# Carte_USB.net
KiCad netlist of a schematic drawn in EAGLE
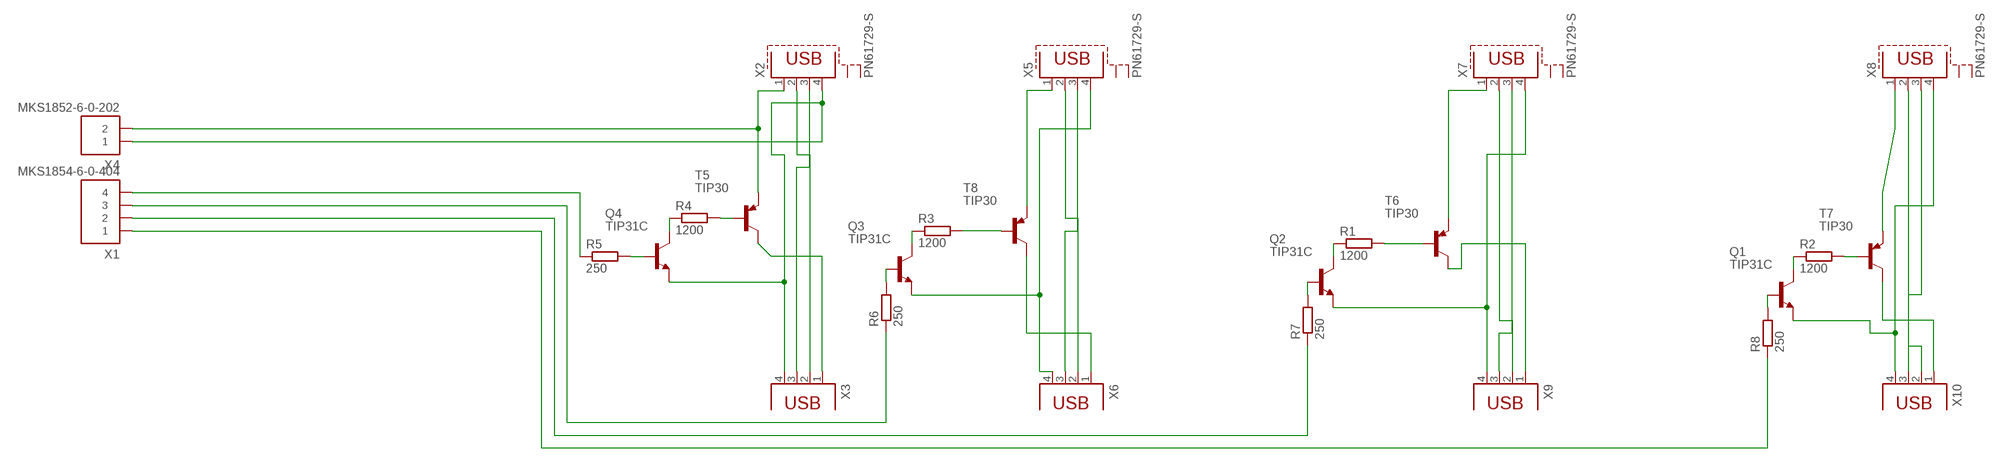
[diagram p0: schematic, sheet 1]

(export (version "E")
  (design (tool "Eeschema 10.0.6"))
  (components
    (comp (ref "Q1")
      (value "TIP31C")
      (footprint "eagle-import:TO220")
      (libsource (lib "eagle-import") (part "TIP31C"))
    )
    (comp (ref "Q2")
      (value "TIP31C")
      (footprint "eagle-import:TO220")
      (libsource (lib "eagle-import") (part "TIP31C"))
    )
    (comp (ref "Q3")
      (value "TIP31C")
      (footprint "eagle-import:TO220")
      (libsource (lib "eagle-import") (part "TIP31C"))
    )
    (comp (ref "Q4")
      (value "TIP31C")
      (footprint "eagle-import:TO220")
      (libsource (lib "eagle-import") (part "TIP31C"))
    )
    (comp (ref "R1")
      (value "1200")
      (footprint "eagle-import:0207_10")
      (libsource (lib "eagle-import") (part "R-EU_0207/10"))
    )
    (comp (ref "R2")
      (value "1200")
      (footprint "eagle-import:0207_10")
      (libsource (lib "eagle-import") (part "R-EU_0207/10"))
    )
    (comp (ref "R3")
      (value "1200")
      (footprint "eagle-import:0207_10")
      (libsource (lib "eagle-import") (part "R-EU_0207/10"))
    )
    (comp (ref "R4")
      (value "1200")
      (footprint "eagle-import:0207_10")
      (libsource (lib "eagle-import") (part "R-EU_0207/10"))
    )
    (comp (ref "R5")
      (value "250")
      (footprint "eagle-import:0207_10")
      (libsource (lib "eagle-import") (part "R-EU_0207/10"))
    )
    (comp (ref "R6")
      (value "250")
      (footprint "eagle-import:0207_12")
      (libsource (lib "eagle-import") (part "R-EU_0207/12"))
    )
    (comp (ref "R7")
      (value "250")
      (footprint "eagle-import:0207_10")
      (libsource (lib "eagle-import") (part "R-EU_0207/10"))
    )
    (comp (ref "R8")
      (value "250")
      (footprint "eagle-import:0207_10")
      (libsource (lib "eagle-import") (part "R-EU_0207/10"))
    )
    (comp (ref "T5")
      (value "TIP30")
      (footprint "eagle-import:TO220")
      (libsource (lib "eagle-import") (part "TIP30"))
    )
    (comp (ref "T6")
      (value "TIP30")
      (footprint "eagle-import:TO220")
      (libsource (lib "eagle-import") (part "TIP30"))
    )
    (comp (ref "T7")
      (value "TIP30")
      (footprint "eagle-import:TO220")
      (libsource (lib "eagle-import") (part "TIP30"))
    )
    (comp (ref "T8")
      (value "TIP30")
      (footprint "eagle-import:TO220")
      (libsource (lib "eagle-import") (part "TIP30"))
    )
    (comp (ref "X1")
      (value "MKS1854-6-0-404")
      (footprint "eagle-import:MKS1854-6-0-404")
      (libsource (lib "eagle-import") (part "MKS1854-6-0-404"))
    )
    (comp (ref "X2")
      (value "PN61729-S")
      (footprint "eagle-import:PN61729-S")
      (libsource (lib "eagle-import") (part "PN61729-S"))
    )
    (comp (ref "X3")
      (value "PN87520")
      (footprint "eagle-import:PN87520")
      (libsource (lib "eagle-import") (part "PN87520"))
    )
    (comp (ref "X4")
      (value "MKS1852-6-0-202")
      (footprint "eagle-import:MKS1852-6-0-202")
      (libsource (lib "eagle-import") (part "MKS1852-6-0-202"))
    )
    (comp (ref "X5")
      (value "PN61729-S")
      (footprint "eagle-import:PN61729-S")
      (libsource (lib "eagle-import") (part "PN61729-S"))
    )
    (comp (ref "X6")
      (value "PN87520")
      (footprint "eagle-import:PN87520")
      (libsource (lib "eagle-import") (part "PN87520"))
    )
    (comp (ref "X7")
      (value "PN61729-S")
      (footprint "eagle-import:PN61729-S")
      (libsource (lib "eagle-import") (part "PN61729-S"))
    )
    (comp (ref "X8")
      (value "PN61729-S")
      (footprint "eagle-import:PN61729-S")
      (libsource (lib "eagle-import") (part "PN61729-S"))
    )
    (comp (ref "X9")
      (value "PN87520")
      (footprint "eagle-import:PN87520")
      (libsource (lib "eagle-import") (part "PN87520"))
    )
    (comp (ref "X10")
      (value "PN87520")
      (footprint "eagle-import:PN87520")
      (libsource (lib "eagle-import") (part "PN87520"))
    )
  )
  (nets
    (net (code "1") (name "Net-(Q1-B)") (class "Default")
      (node (ref "Q1") (pin "1") (pinfunction "B_1") (pintype "passive"))
      (node (ref "R8") (pin "2") (pinfunction "2_2") (pintype "passive"))
    )
    (net (code "2") (name "Net-(Q1-C)") (class "Default")
      (node (ref "Q1") (pin "2") (pinfunction "C_2") (pintype "passive"))
      (node (ref "R2") (pin "1") (pinfunction "1_1") (pintype "passive"))
    )
    (net (code "3") (name "Net-(Q1-E)") (class "Default")
      (node (ref "Q1") (pin "3") (pinfunction "E_3") (pintype "passive"))
      (node (ref "X10") (pin "4") (pinfunction "4_4") (pintype "passive"))
      (node (ref "X8") (pin "4") (pinfunction "4_4") (pintype "passive"))
    )
    (net (code "4") (name "Net-(Q2-B)") (class "Default")
      (node (ref "Q2") (pin "1") (pinfunction "B_1") (pintype "passive"))
      (node (ref "R7") (pin "2") (pinfunction "2_2") (pintype "passive"))
    )
    (net (code "5") (name "Net-(Q2-C)") (class "Default")
      (node (ref "Q2") (pin "2") (pinfunction "C_2") (pintype "passive"))
      (node (ref "R1") (pin "1") (pinfunction "1_1") (pintype "passive"))
    )
    (net (code "6") (name "Net-(Q2-E)") (class "Default")
      (node (ref "Q2") (pin "3") (pinfunction "E_3") (pintype "passive"))
      (node (ref "X7") (pin "4") (pinfunction "4_4") (pintype "passive"))
      (node (ref "X9") (pin "4") (pinfunction "4_4") (pintype "passive"))
    )
    (net (code "7") (name "Net-(Q3-B)") (class "Default")
      (node (ref "Q3") (pin "1") (pinfunction "B_1") (pintype "passive"))
      (node (ref "R6") (pin "2") (pinfunction "2_2") (pintype "passive"))
    )
    (net (code "8") (name "Net-(Q3-C)") (class "Default")
      (node (ref "Q3") (pin "2") (pinfunction "C_2") (pintype "passive"))
      (node (ref "R3") (pin "1") (pinfunction "1_1") (pintype "passive"))
    )
    (net (code "9") (name "Net-(Q3-E)") (class "Default")
      (node (ref "Q3") (pin "3") (pinfunction "E_3") (pintype "passive"))
      (node (ref "X5") (pin "4") (pinfunction "4_4") (pintype "passive"))
      (node (ref "X6") (pin "4") (pinfunction "4_4") (pintype "passive"))
    )
    (net (code "10") (name "Net-(Q4-B)") (class "Default")
      (node (ref "Q4") (pin "1") (pinfunction "B_1") (pintype "passive"))
      (node (ref "R5") (pin "2") (pinfunction "2_2") (pintype "passive"))
    )
    (net (code "11") (name "Net-(Q4-C)") (class "Default")
      (node (ref "Q4") (pin "2") (pinfunction "C_2") (pintype "passive"))
      (node (ref "R4") (pin "1") (pinfunction "1_1") (pintype "passive"))
    )
    (net (code "12") (name "Net-(Q4-E)") (class "Default")
      (node (ref "Q4") (pin "3") (pinfunction "E_3") (pintype "passive"))
      (node (ref "X2") (pin "4") (pinfunction "4_4") (pintype "passive"))
      (node (ref "X3") (pin "4") (pinfunction "4_4") (pintype "passive"))
      (node (ref "X4") (pin "1") (pinfunction "1_1") (pintype "input"))
    )
    (net (code "13") (name "Net-(R5-Pad1)") (class "Default")
      (node (ref "R5") (pin "1") (pinfunction "1_1") (pintype "passive"))
      (node (ref "X1") (pin "4") (pinfunction "4_4") (pintype "input"))
    )
    (net (code "14") (name "Net-(R6-Pad1)") (class "Default")
      (node (ref "R6") (pin "1") (pinfunction "1_1") (pintype "passive"))
      (node (ref "X1") (pin "3") (pinfunction "3_3") (pintype "input"))
    )
    (net (code "15") (name "Net-(R7-Pad1)") (class "Default")
      (node (ref "R7") (pin "1") (pinfunction "1_1") (pintype "passive"))
      (node (ref "X1") (pin "2") (pinfunction "2_2") (pintype "input"))
    )
    (net (code "16") (name "Net-(R8-Pad1)") (class "Default")
      (node (ref "R8") (pin "1") (pinfunction "1_1") (pintype "passive"))
      (node (ref "X1") (pin "1") (pinfunction "1_1") (pintype "input"))
    )
    (net (code "17") (name "Net-(T5-B)") (class "Default")
      (node (ref "R4") (pin "2") (pinfunction "2_2") (pintype "passive"))
      (node (ref "T5") (pin "1") (pinfunction "B_1") (pintype "passive"))
    )
    (net (code "18") (name "Net-(T5-C)") (class "Default")
      (node (ref "T5") (pin "2") (pinfunction "C_2") (pintype "passive"))
      (node (ref "X3") (pin "1") (pinfunction "1_1") (pintype "passive"))
    )
    (net (code "19") (name "Net-(T5-E)") (class "Default")
      (node (ref "T5") (pin "3") (pinfunction "E_3") (pintype "passive"))
      (node (ref "X2") (pin "1") (pinfunction "1_1") (pintype "passive"))
      (node (ref "X4") (pin "2") (pinfunction "2_2") (pintype "input"))
    )
    (net (code "20") (name "Net-(T6-B)") (class "Default")
      (node (ref "R1") (pin "2") (pinfunction "2_2") (pintype "passive"))
      (node (ref "T6") (pin "1") (pinfunction "B_1") (pintype "passive"))
    )
    (net (code "21") (name "Net-(T6-C)") (class "Default")
      (node (ref "T6") (pin "2") (pinfunction "C_2") (pintype "passive"))
      (node (ref "X9") (pin "1") (pinfunction "1_1") (pintype "passive"))
    )
    (net (code "22") (name "Net-(T6-E)") (class "Default")
      (node (ref "T6") (pin "3") (pinfunction "E_3") (pintype "passive"))
      (node (ref "X7") (pin "1") (pinfunction "1_1") (pintype "passive"))
    )
    (net (code "23") (name "Net-(T7-B)") (class "Default")
      (node (ref "R2") (pin "2") (pinfunction "2_2") (pintype "passive"))
      (node (ref "T7") (pin "1") (pinfunction "B_1") (pintype "passive"))
    )
    (net (code "24") (name "Net-(T7-C)") (class "Default")
      (node (ref "T7") (pin "2") (pinfunction "C_2") (pintype "passive"))
      (node (ref "X10") (pin "1") (pinfunction "1_1") (pintype "passive"))
    )
    (net (code "25") (name "Net-(T7-E)") (class "Default")
      (node (ref "T7") (pin "3") (pinfunction "E_3") (pintype "passive"))
      (node (ref "X8") (pin "1") (pinfunction "1_1") (pintype "passive"))
    )
    (net (code "26") (name "Net-(T8-B)") (class "Default")
      (node (ref "R3") (pin "2") (pinfunction "2_2") (pintype "passive"))
      (node (ref "T8") (pin "1") (pinfunction "B_1") (pintype "passive"))
    )
    (net (code "27") (name "Net-(T8-C)") (class "Default")
      (node (ref "T8") (pin "2") (pinfunction "C_2") (pintype "passive"))
      (node (ref "X6") (pin "1") (pinfunction "1_1") (pintype "passive"))
    )
    (net (code "28") (name "Net-(T8-E)") (class "Default")
      (node (ref "T8") (pin "3") (pinfunction "E_3") (pintype "passive"))
      (node (ref "X5") (pin "1") (pinfunction "1_1") (pintype "passive"))
    )
    (net (code "29") (name "Net-(X2-Pad2)") (class "Default")
      (node (ref "X2") (pin "2") (pinfunction "2_2") (pintype "passive"))
      (node (ref "X3") (pin "2") (pinfunction "2_2") (pintype "passive"))
    )
    (net (code "30") (name "Net-(X2-Pad3)") (class "Default")
      (node (ref "X2") (pin "3") (pinfunction "3_3") (pintype "passive"))
      (node (ref "X3") (pin "3") (pinfunction "3_3") (pintype "passive"))
    )
    (net (code "31") (name "Net-(X5-Pad2)") (class "Default")
      (node (ref "X5") (pin "2") (pinfunction "2_2") (pintype "passive"))
      (node (ref "X6") (pin "2") (pinfunction "2_2") (pintype "passive"))
    )
    (net (code "32") (name "Net-(X5-Pad3)") (class "Default")
      (node (ref "X5") (pin "3") (pinfunction "3_3") (pintype "passive"))
      (node (ref "X6") (pin "3") (pinfunction "3_3") (pintype "passive"))
    )
    (net (code "33") (name "Net-(X7-Pad2)") (class "Default")
      (node (ref "X7") (pin "2") (pinfunction "2_2") (pintype "passive"))
      (node (ref "X9") (pin "2") (pinfunction "2_2") (pintype "passive"))
    )
    (net (code "34") (name "Net-(X7-Pad3)") (class "Default")
      (node (ref "X7") (pin "3") (pinfunction "3_3") (pintype "passive"))
      (node (ref "X9") (pin "3") (pinfunction "3_3") (pintype "passive"))
    )
    (net (code "35") (name "Net-(X10-Pad2)") (class "Default")
      (node (ref "X10") (pin "2") (pinfunction "2_2") (pintype "passive"))
      (node (ref "X8") (pin "2") (pinfunction "2_2") (pintype "passive"))
    )
    (net (code "36") (name "Net-(X10-Pad3)") (class "Default")
      (node (ref "X10") (pin "3") (pinfunction "3_3") (pintype "passive"))
      (node (ref "X8") (pin "3") (pinfunction "3_3") (pintype "passive"))
    )
    (net (code "37") (name "unconnected-(X2-PadS1)") (class "Default")
      (node (ref "X2") (pin "S1") (pinfunction "S1_S1") (pintype "passive"))
    )
    (net (code "38") (name "unconnected-(X2-PadS2)") (class "Default")
      (node (ref "X2") (pin "S2") (pinfunction "S2_S2") (pintype "passive"))
    )
    (net (code "39") (name "unconnected-(X5-PadS1)") (class "Default")
      (node (ref "X5") (pin "S1") (pinfunction "S1_S1") (pintype "passive"))
    )
    (net (code "40") (name "unconnected-(X5-PadS2)") (class "Default")
      (node (ref "X5") (pin "S2") (pinfunction "S2_S2") (pintype "passive"))
    )
    (net (code "41") (name "unconnected-(X7-PadS1)") (class "Default")
      (node (ref "X7") (pin "S1") (pinfunction "S1_S1") (pintype "passive"))
    )
    (net (code "42") (name "unconnected-(X7-PadS2)") (class "Default")
      (node (ref "X7") (pin "S2") (pinfunction "S2_S2") (pintype "passive"))
    )
    (net (code "43") (name "unconnected-(X8-PadS1)") (class "Default")
      (node (ref "X8") (pin "S1") (pinfunction "S1_S1") (pintype "passive"))
    )
    (net (code "44") (name "unconnected-(X8-PadS2)") (class "Default")
      (node (ref "X8") (pin "S2") (pinfunction "S2_S2") (pintype "passive"))
    )
  )
)
